# SIK-DIP-board.net
KiCad netlist of a schematic drawn in Altium Designer
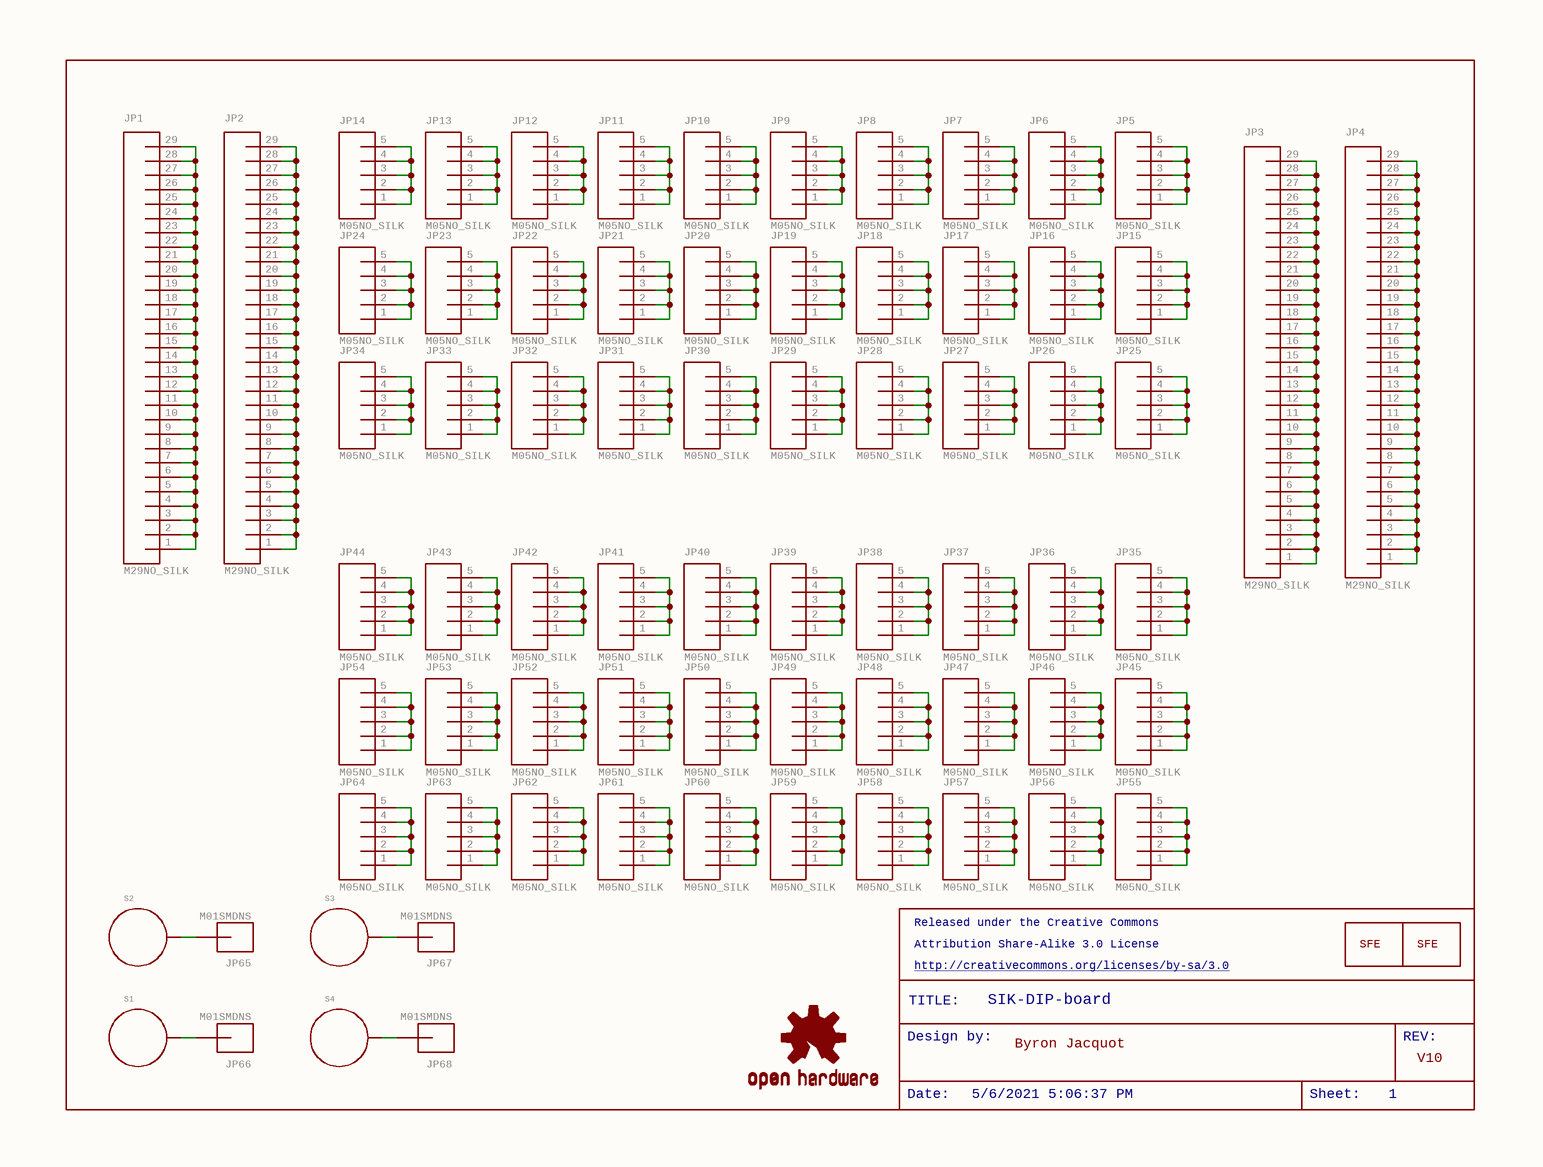
[diagram p0: SIK-DIP-board.SchDoc]

(export (version "E")
  (design (tool "Eeschema 10.0.6"))
  (components
    (comp (ref "JP1")
      (value "M29NO_SILK")
      (footprint "1X29_NO_SILK")
      (description "1x29 .1\" header")
      (libsource (lib "SparkFun-Connectors") (part "M29NO_SILK"))
    )
    (comp (ref "JP2")
      (value "M29NO_SILK")
      (footprint "1X29_NO_SILK")
      (description "1x29 .1\" header")
      (libsource (lib "SparkFun-Connectors") (part "M29NO_SILK"))
    )
    (comp (ref "JP3")
      (value "M29NO_SILK")
      (footprint "1X29_NO_SILK")
      (description "1x29 .1\" header")
      (libsource (lib "SparkFun-Connectors") (part "M29NO_SILK"))
    )
    (comp (ref "JP4")
      (value "M29NO_SILK")
      (footprint "1X29_NO_SILK")
      (description "1x29 .1\" header")
      (libsource (lib "SparkFun-Connectors") (part "M29NO_SILK"))
    )
    (comp (ref "JP5")
      (value "M05NO_SILK")
      (footprint "1X05_NO_SILK")
      (libsource (lib "SparkFun-Connectors") (part "M05NO_SILK"))
    )
    (comp (ref "JP6")
      (value "M05NO_SILK")
      (footprint "1X05_NO_SILK")
      (libsource (lib "SparkFun-Connectors") (part "M05NO_SILK"))
    )
    (comp (ref "JP7")
      (value "M05NO_SILK")
      (footprint "1X05_NO_SILK")
      (libsource (lib "SparkFun-Connectors") (part "M05NO_SILK"))
    )
    (comp (ref "JP8")
      (value "M05NO_SILK")
      (footprint "1X05_NO_SILK")
      (libsource (lib "SparkFun-Connectors") (part "M05NO_SILK"))
    )
    (comp (ref "JP9")
      (value "M05NO_SILK")
      (footprint "1X05_NO_SILK")
      (libsource (lib "SparkFun-Connectors") (part "M05NO_SILK"))
    )
    (comp (ref "JP10")
      (value "M05NO_SILK")
      (footprint "1X05_NO_SILK")
      (libsource (lib "SparkFun-Connectors") (part "M05NO_SILK"))
    )
    (comp (ref "JP11")
      (value "M05NO_SILK")
      (footprint "1X05_NO_SILK")
      (libsource (lib "SparkFun-Connectors") (part "M05NO_SILK"))
    )
    (comp (ref "JP12")
      (value "M05NO_SILK")
      (footprint "1X05_NO_SILK")
      (libsource (lib "SparkFun-Connectors") (part "M05NO_SILK"))
    )
    (comp (ref "JP13")
      (value "M05NO_SILK")
      (footprint "1X05_NO_SILK")
      (libsource (lib "SparkFun-Connectors") (part "M05NO_SILK"))
    )
    (comp (ref "JP14")
      (value "M05NO_SILK")
      (footprint "1X05_NO_SILK")
      (libsource (lib "SparkFun-Connectors") (part "M05NO_SILK"))
    )
    (comp (ref "JP15")
      (value "M05NO_SILK")
      (footprint "1X05_NO_SILK")
      (libsource (lib "SparkFun-Connectors") (part "M05NO_SILK"))
    )
    (comp (ref "JP16")
      (value "M05NO_SILK")
      (footprint "1X05_NO_SILK")
      (libsource (lib "SparkFun-Connectors") (part "M05NO_SILK"))
    )
    (comp (ref "JP17")
      (value "M05NO_SILK")
      (footprint "1X05_NO_SILK")
      (libsource (lib "SparkFun-Connectors") (part "M05NO_SILK"))
    )
    (comp (ref "JP18")
      (value "M05NO_SILK")
      (footprint "1X05_NO_SILK")
      (libsource (lib "SparkFun-Connectors") (part "M05NO_SILK"))
    )
    (comp (ref "JP19")
      (value "M05NO_SILK")
      (footprint "1X05_NO_SILK")
      (libsource (lib "SparkFun-Connectors") (part "M05NO_SILK"))
    )
    (comp (ref "JP20")
      (value "M05NO_SILK")
      (footprint "1X05_NO_SILK")
      (libsource (lib "SparkFun-Connectors") (part "M05NO_SILK"))
    )
    (comp (ref "JP21")
      (value "M05NO_SILK")
      (footprint "1X05_NO_SILK")
      (libsource (lib "SparkFun-Connectors") (part "M05NO_SILK"))
    )
    (comp (ref "JP22")
      (value "M05NO_SILK")
      (footprint "1X05_NO_SILK")
      (libsource (lib "SparkFun-Connectors") (part "M05NO_SILK"))
    )
    (comp (ref "JP23")
      (value "M05NO_SILK")
      (footprint "1X05_NO_SILK")
      (libsource (lib "SparkFun-Connectors") (part "M05NO_SILK"))
    )
    (comp (ref "JP24")
      (value "M05NO_SILK")
      (footprint "1X05_NO_SILK")
      (libsource (lib "SparkFun-Connectors") (part "M05NO_SILK"))
    )
    (comp (ref "JP25")
      (value "M05NO_SILK")
      (footprint "1X05_NO_SILK")
      (libsource (lib "SparkFun-Connectors") (part "M05NO_SILK"))
    )
    (comp (ref "JP26")
      (value "M05NO_SILK")
      (footprint "1X05_NO_SILK")
      (libsource (lib "SparkFun-Connectors") (part "M05NO_SILK"))
    )
    (comp (ref "JP27")
      (value "M05NO_SILK")
      (footprint "1X05_NO_SILK")
      (libsource (lib "SparkFun-Connectors") (part "M05NO_SILK"))
    )
    (comp (ref "JP28")
      (value "M05NO_SILK")
      (footprint "1X05_NO_SILK")
      (libsource (lib "SparkFun-Connectors") (part "M05NO_SILK"))
    )
    (comp (ref "JP29")
      (value "M05NO_SILK")
      (footprint "1X05_NO_SILK")
      (libsource (lib "SparkFun-Connectors") (part "M05NO_SILK"))
    )
    (comp (ref "JP30")
      (value "M05NO_SILK")
      (footprint "1X05_NO_SILK")
      (libsource (lib "SparkFun-Connectors") (part "M05NO_SILK"))
    )
    (comp (ref "JP31")
      (value "M05NO_SILK")
      (footprint "1X05_NO_SILK")
      (libsource (lib "SparkFun-Connectors") (part "M05NO_SILK"))
    )
    (comp (ref "JP32")
      (value "M05NO_SILK")
      (footprint "1X05_NO_SILK")
      (libsource (lib "SparkFun-Connectors") (part "M05NO_SILK"))
    )
    (comp (ref "JP33")
      (value "M05NO_SILK")
      (footprint "1X05_NO_SILK")
      (libsource (lib "SparkFun-Connectors") (part "M05NO_SILK"))
    )
    (comp (ref "JP34")
      (value "M05NO_SILK")
      (footprint "1X05_NO_SILK")
      (libsource (lib "SparkFun-Connectors") (part "M05NO_SILK"))
    )
    (comp (ref "JP35")
      (value "M05NO_SILK")
      (footprint "1X05_NO_SILK")
      (libsource (lib "SparkFun-Connectors") (part "M05NO_SILK"))
    )
    (comp (ref "JP36")
      (value "M05NO_SILK")
      (footprint "1X05_NO_SILK")
      (libsource (lib "SparkFun-Connectors") (part "M05NO_SILK"))
    )
    (comp (ref "JP37")
      (value "M05NO_SILK")
      (footprint "1X05_NO_SILK")
      (libsource (lib "SparkFun-Connectors") (part "M05NO_SILK"))
    )
    (comp (ref "JP38")
      (value "M05NO_SILK")
      (footprint "1X05_NO_SILK")
      (libsource (lib "SparkFun-Connectors") (part "M05NO_SILK"))
    )
    (comp (ref "JP39")
      (value "M05NO_SILK")
      (footprint "1X05_NO_SILK")
      (libsource (lib "SparkFun-Connectors") (part "M05NO_SILK"))
    )
    (comp (ref "JP40")
      (value "M05NO_SILK")
      (footprint "1X05_NO_SILK")
      (libsource (lib "SparkFun-Connectors") (part "M05NO_SILK"))
    )
    (comp (ref "JP41")
      (value "M05NO_SILK")
      (footprint "1X05_NO_SILK")
      (libsource (lib "SparkFun-Connectors") (part "M05NO_SILK"))
    )
    (comp (ref "JP42")
      (value "M05NO_SILK")
      (footprint "1X05_NO_SILK")
      (libsource (lib "SparkFun-Connectors") (part "M05NO_SILK"))
    )
    (comp (ref "JP43")
      (value "M05NO_SILK")
      (footprint "1X05_NO_SILK")
      (libsource (lib "SparkFun-Connectors") (part "M05NO_SILK"))
    )
    (comp (ref "JP44")
      (value "M05NO_SILK")
      (footprint "1X05_NO_SILK")
      (libsource (lib "SparkFun-Connectors") (part "M05NO_SILK"))
    )
    (comp (ref "JP45")
      (value "M05NO_SILK")
      (footprint "1X05_NO_SILK")
      (libsource (lib "SparkFun-Connectors") (part "M05NO_SILK"))
    )
    (comp (ref "JP46")
      (value "M05NO_SILK")
      (footprint "1X05_NO_SILK")
      (libsource (lib "SparkFun-Connectors") (part "M05NO_SILK"))
    )
    (comp (ref "JP47")
      (value "M05NO_SILK")
      (footprint "1X05_NO_SILK")
      (libsource (lib "SparkFun-Connectors") (part "M05NO_SILK"))
    )
    (comp (ref "JP48")
      (value "M05NO_SILK")
      (footprint "1X05_NO_SILK")
      (libsource (lib "SparkFun-Connectors") (part "M05NO_SILK"))
    )
    (comp (ref "JP49")
      (value "M05NO_SILK")
      (footprint "1X05_NO_SILK")
      (libsource (lib "SparkFun-Connectors") (part "M05NO_SILK"))
    )
    (comp (ref "JP50")
      (value "M05NO_SILK")
      (footprint "1X05_NO_SILK")
      (libsource (lib "SparkFun-Connectors") (part "M05NO_SILK"))
    )
    (comp (ref "JP51")
      (value "M05NO_SILK")
      (footprint "1X05_NO_SILK")
      (libsource (lib "SparkFun-Connectors") (part "M05NO_SILK"))
    )
    (comp (ref "JP52")
      (value "M05NO_SILK")
      (footprint "1X05_NO_SILK")
      (libsource (lib "SparkFun-Connectors") (part "M05NO_SILK"))
    )
    (comp (ref "JP53")
      (value "M05NO_SILK")
      (footprint "1X05_NO_SILK")
      (libsource (lib "SparkFun-Connectors") (part "M05NO_SILK"))
    )
    (comp (ref "JP54")
      (value "M05NO_SILK")
      (footprint "1X05_NO_SILK")
      (libsource (lib "SparkFun-Connectors") (part "M05NO_SILK"))
    )
    (comp (ref "JP55")
      (value "M05NO_SILK")
      (footprint "1X05_NO_SILK")
      (libsource (lib "SparkFun-Connectors") (part "M05NO_SILK"))
    )
    (comp (ref "JP56")
      (value "M05NO_SILK")
      (footprint "1X05_NO_SILK")
      (libsource (lib "SparkFun-Connectors") (part "M05NO_SILK"))
    )
    (comp (ref "JP57")
      (value "M05NO_SILK")
      (footprint "1X05_NO_SILK")
      (libsource (lib "SparkFun-Connectors") (part "M05NO_SILK"))
    )
    (comp (ref "JP58")
      (value "M05NO_SILK")
      (footprint "1X05_NO_SILK")
      (libsource (lib "SparkFun-Connectors") (part "M05NO_SILK"))
    )
    (comp (ref "JP59")
      (value "M05NO_SILK")
      (footprint "1X05_NO_SILK")
      (libsource (lib "SparkFun-Connectors") (part "M05NO_SILK"))
    )
    (comp (ref "JP60")
      (value "M05NO_SILK")
      (footprint "1X05_NO_SILK")
      (libsource (lib "SparkFun-Connectors") (part "M05NO_SILK"))
    )
    (comp (ref "JP61")
      (value "M05NO_SILK")
      (footprint "1X05_NO_SILK")
      (libsource (lib "SparkFun-Connectors") (part "M05NO_SILK"))
    )
    (comp (ref "JP62")
      (value "M05NO_SILK")
      (footprint "1X05_NO_SILK")
      (libsource (lib "SparkFun-Connectors") (part "M05NO_SILK"))
    )
    (comp (ref "JP63")
      (value "M05NO_SILK")
      (footprint "1X05_NO_SILK")
      (libsource (lib "SparkFun-Connectors") (part "M05NO_SILK"))
    )
    (comp (ref "JP64")
      (value "M05NO_SILK")
      (footprint "1X05_NO_SILK")
      (libsource (lib "SparkFun-Connectors") (part "M05NO_SILK"))
    )
    (comp (ref "JP65")
      (value "M01SMDNS")
      (footprint "1X01NS")
      (libsource (lib "SparkFun-Connectors") (part "M01SMDNS"))
    )
    (comp (ref "JP66")
      (value "M01SMDNS")
      (footprint "1X01NS")
      (libsource (lib "SparkFun-Connectors") (part "M01SMDNS"))
    )
    (comp (ref "JP67")
      (value "M01SMDNS")
      (footprint "1X01NS")
      (libsource (lib "SparkFun-Connectors") (part "M01SMDNS"))
    )
    (comp (ref "JP68")
      (value "M01SMDNS")
      (footprint "1X01NS")
      (libsource (lib "SparkFun-Connectors") (part "M01SMDNS"))
    )
    (comp (ref "LOGO1")
      (value "LOGO-SFECP")
      (footprint "SFE-LOGO-FLAME-COPPER")
      (description "Spark Fun Electronics PCB LogoThis is the standard Spark Fun Electronics PCB logo.")
      (fields (field (name "SFE") "SFE"))
      (libsource (lib "SparkFun-Aesthetics") (part "LOGO-SFECP"))
    )
    (comp (ref "LOGO2")
      (value "LOGO-SFENEW")
      (footprint "SFE-NEW-WEBLOGO")
      (description "Spark Fun Electronics PCB LogoThis is the standard Spark Fun Electronics PCB logo.")
      (fields (field (name "SFE") "SFE"))
      (libsource (lib "SparkFun-Aesthetics") (part "LOGO-SFENEW"))
    )
    (comp (ref "LOGO3")
      (value "OSHW-LOGOS")
      (footprint "OSHW-LOGO-S")
      (libsource (lib "SparkFun-Aesthetics") (part "OSHW-LOGOS"))
    )
    (comp (ref "S1")
      (value "STANDOFF_ELECTRICAL")
      (footprint "STANDOFF-ELECTRICAL")
      (libsource (lib "SparkFun-Electromechanical") (part "STANDOFF_ELECTRICAL"))
    )
    (comp (ref "S2")
      (value "STANDOFF_ELECTRICAL")
      (footprint "STANDOFF-ELECTRICAL")
      (libsource (lib "SparkFun-Electromechanical") (part "STANDOFF_ELECTRICAL"))
    )
    (comp (ref "S3")
      (value "STANDOFF_ELECTRICAL")
      (footprint "STANDOFF-ELECTRICAL")
      (libsource (lib "SparkFun-Electromechanical") (part "STANDOFF_ELECTRICAL"))
    )
    (comp (ref "S4")
      (value "STANDOFF_ELECTRICAL")
      (footprint "STANDOFF-ELECTRICAL")
      (libsource (lib "SparkFun-Electromechanical") (part "STANDOFF_ELECTRICAL"))
    )
  )
  (nets
    (net (code "1") (name "Net-(JP1-Pad1)") (class "Default")
      (node (ref "JP1") (pin "1") (pinfunction "1_1") (pintype "passive"))
      (node (ref "JP1") (pin "10") (pinfunction "10_10") (pintype "passive"))
      (node (ref "JP1") (pin "11") (pinfunction "11_11") (pintype "passive"))
      (node (ref "JP1") (pin "12") (pinfunction "12_12") (pintype "passive"))
      (node (ref "JP1") (pin "13") (pinfunction "13_13") (pintype "passive"))
      (node (ref "JP1") (pin "14") (pinfunction "14_14") (pintype "passive"))
      (node (ref "JP1") (pin "15") (pinfunction "15_15") (pintype "passive"))
      (node (ref "JP1") (pin "16") (pinfunction "16_16") (pintype "passive"))
      (node (ref "JP1") (pin "17") (pinfunction "17_17") (pintype "passive"))
      (node (ref "JP1") (pin "18") (pinfunction "18_18") (pintype "passive"))
      (node (ref "JP1") (pin "19") (pinfunction "19_19") (pintype "passive"))
      (node (ref "JP1") (pin "2") (pinfunction "2_2") (pintype "passive"))
      (node (ref "JP1") (pin "20") (pinfunction "20_20") (pintype "passive"))
      (node (ref "JP1") (pin "21") (pinfunction "21_21") (pintype "passive"))
      (node (ref "JP1") (pin "22") (pinfunction "22_22") (pintype "passive"))
      (node (ref "JP1") (pin "23") (pinfunction "23_23") (pintype "passive"))
      (node (ref "JP1") (pin "24") (pinfunction "24_24") (pintype "passive"))
      (node (ref "JP1") (pin "25") (pinfunction "25_25") (pintype "passive"))
      (node (ref "JP1") (pin "26") (pinfunction "26_26") (pintype "passive"))
      (node (ref "JP1") (pin "27") (pinfunction "27_27") (pintype "passive"))
      (node (ref "JP1") (pin "28") (pinfunction "28_28") (pintype "passive"))
      (node (ref "JP1") (pin "29") (pinfunction "29_29") (pintype "passive"))
      (node (ref "JP1") (pin "3") (pinfunction "3_3") (pintype "passive"))
      (node (ref "JP1") (pin "4") (pinfunction "4_4") (pintype "passive"))
      (node (ref "JP1") (pin "5") (pinfunction "5_5") (pintype "passive"))
      (node (ref "JP1") (pin "6") (pinfunction "6_6") (pintype "passive"))
      (node (ref "JP1") (pin "7") (pinfunction "7_7") (pintype "passive"))
      (node (ref "JP1") (pin "8") (pinfunction "8_8") (pintype "passive"))
      (node (ref "JP1") (pin "9") (pinfunction "9_9") (pintype "passive"))
    )
    (net (code "2") (name "Net-(JP2-Pad1)") (class "Default")
      (node (ref "JP2") (pin "1") (pinfunction "1_1") (pintype "passive"))
      (node (ref "JP2") (pin "10") (pinfunction "10_10") (pintype "passive"))
      (node (ref "JP2") (pin "11") (pinfunction "11_11") (pintype "passive"))
      (node (ref "JP2") (pin "12") (pinfunction "12_12") (pintype "passive"))
      (node (ref "JP2") (pin "13") (pinfunction "13_13") (pintype "passive"))
      (node (ref "JP2") (pin "14") (pinfunction "14_14") (pintype "passive"))
      (node (ref "JP2") (pin "15") (pinfunction "15_15") (pintype "passive"))
      (node (ref "JP2") (pin "16") (pinfunction "16_16") (pintype "passive"))
      (node (ref "JP2") (pin "17") (pinfunction "17_17") (pintype "passive"))
      (node (ref "JP2") (pin "18") (pinfunction "18_18") (pintype "passive"))
      (node (ref "JP2") (pin "19") (pinfunction "19_19") (pintype "passive"))
      (node (ref "JP2") (pin "2") (pinfunction "2_2") (pintype "passive"))
      (node (ref "JP2") (pin "20") (pinfunction "20_20") (pintype "passive"))
      (node (ref "JP2") (pin "21") (pinfunction "21_21") (pintype "passive"))
      (node (ref "JP2") (pin "22") (pinfunction "22_22") (pintype "passive"))
      (node (ref "JP2") (pin "23") (pinfunction "23_23") (pintype "passive"))
      (node (ref "JP2") (pin "24") (pinfunction "24_24") (pintype "passive"))
      (node (ref "JP2") (pin "25") (pinfunction "25_25") (pintype "passive"))
      (node (ref "JP2") (pin "26") (pinfunction "26_26") (pintype "passive"))
      (node (ref "JP2") (pin "27") (pinfunction "27_27") (pintype "passive"))
      (node (ref "JP2") (pin "28") (pinfunction "28_28") (pintype "passive"))
      (node (ref "JP2") (pin "29") (pinfunction "29_29") (pintype "passive"))
      (node (ref "JP2") (pin "3") (pinfunction "3_3") (pintype "passive"))
      (node (ref "JP2") (pin "4") (pinfunction "4_4") (pintype "passive"))
      (node (ref "JP2") (pin "5") (pinfunction "5_5") (pintype "passive"))
      (node (ref "JP2") (pin "6") (pinfunction "6_6") (pintype "passive"))
      (node (ref "JP2") (pin "7") (pinfunction "7_7") (pintype "passive"))
      (node (ref "JP2") (pin "8") (pinfunction "8_8") (pintype "passive"))
      (node (ref "JP2") (pin "9") (pinfunction "9_9") (pintype "passive"))
    )
    (net (code "3") (name "Net-(JP3-Pad1)") (class "Default")
      (node (ref "JP3") (pin "1") (pinfunction "1_1") (pintype "passive"))
      (node (ref "JP3") (pin "10") (pinfunction "10_10") (pintype "passive"))
      (node (ref "JP3") (pin "11") (pinfunction "11_11") (pintype "passive"))
      (node (ref "JP3") (pin "12") (pinfunction "12_12") (pintype "passive"))
      (node (ref "JP3") (pin "13") (pinfunction "13_13") (pintype "passive"))
      (node (ref "JP3") (pin "14") (pinfunction "14_14") (pintype "passive"))
      (node (ref "JP3") (pin "15") (pinfunction "15_15") (pintype "passive"))
      (node (ref "JP3") (pin "16") (pinfunction "16_16") (pintype "passive"))
      (node (ref "JP3") (pin "17") (pinfunction "17_17") (pintype "passive"))
      (node (ref "JP3") (pin "18") (pinfunction "18_18") (pintype "passive"))
      (node (ref "JP3") (pin "19") (pinfunction "19_19") (pintype "passive"))
      (node (ref "JP3") (pin "2") (pinfunction "2_2") (pintype "passive"))
      (node (ref "JP3") (pin "20") (pinfunction "20_20") (pintype "passive"))
      (node (ref "JP3") (pin "21") (pinfunction "21_21") (pintype "passive"))
      (node (ref "JP3") (pin "22") (pinfunction "22_22") (pintype "passive"))
      (node (ref "JP3") (pin "23") (pinfunction "23_23") (pintype "passive"))
      (node (ref "JP3") (pin "24") (pinfunction "24_24") (pintype "passive"))
      (node (ref "JP3") (pin "25") (pinfunction "25_25") (pintype "passive"))
      (node (ref "JP3") (pin "26") (pinfunction "26_26") (pintype "passive"))
      (node (ref "JP3") (pin "27") (pinfunction "27_27") (pintype "passive"))
      (node (ref "JP3") (pin "28") (pinfunction "28_28") (pintype "passive"))
      (node (ref "JP3") (pin "29") (pinfunction "29_29") (pintype "passive"))
      (node (ref "JP3") (pin "3") (pinfunction "3_3") (pintype "passive"))
      (node (ref "JP3") (pin "4") (pinfunction "4_4") (pintype "passive"))
      (node (ref "JP3") (pin "5") (pinfunction "5_5") (pintype "passive"))
      (node (ref "JP3") (pin "6") (pinfunction "6_6") (pintype "passive"))
      (node (ref "JP3") (pin "7") (pinfunction "7_7") (pintype "passive"))
      (node (ref "JP3") (pin "8") (pinfunction "8_8") (pintype "passive"))
      (node (ref "JP3") (pin "9") (pinfunction "9_9") (pintype "passive"))
    )
    (net (code "4") (name "Net-(JP4-Pad1)") (class "Default")
      (node (ref "JP4") (pin "1") (pinfunction "1_1") (pintype "passive"))
      (node (ref "JP4") (pin "10") (pinfunction "10_10") (pintype "passive"))
      (node (ref "JP4") (pin "11") (pinfunction "11_11") (pintype "passive"))
      (node (ref "JP4") (pin "12") (pinfunction "12_12") (pintype "passive"))
      (node (ref "JP4") (pin "13") (pinfunction "13_13") (pintype "passive"))
      (node (ref "JP4") (pin "14") (pinfunction "14_14") (pintype "passive"))
      (node (ref "JP4") (pin "15") (pinfunction "15_15") (pintype "passive"))
      (node (ref "JP4") (pin "16") (pinfunction "16_16") (pintype "passive"))
      (node (ref "JP4") (pin "17") (pinfunction "17_17") (pintype "passive"))
      (node (ref "JP4") (pin "18") (pinfunction "18_18") (pintype "passive"))
      (node (ref "JP4") (pin "19") (pinfunction "19_19") (pintype "passive"))
      (node (ref "JP4") (pin "2") (pinfunction "2_2") (pintype "passive"))
      (node (ref "JP4") (pin "20") (pinfunction "20_20") (pintype "passive"))
      (node (ref "JP4") (pin "21") (pinfunction "21_21") (pintype "passive"))
      (node (ref "JP4") (pin "22") (pinfunction "22_22") (pintype "passive"))
      (node (ref "JP4") (pin "23") (pinfunction "23_23") (pintype "passive"))
      (node (ref "JP4") (pin "24") (pinfunction "24_24") (pintype "passive"))
      (node (ref "JP4") (pin "25") (pinfunction "25_25") (pintype "passive"))
      (node (ref "JP4") (pin "26") (pinfunction "26_26") (pintype "passive"))
      (node (ref "JP4") (pin "27") (pinfunction "27_27") (pintype "passive"))
      (node (ref "JP4") (pin "28") (pinfunction "28_28") (pintype "passive"))
      (node (ref "JP4") (pin "29") (pinfunction "29_29") (pintype "passive"))
      (node (ref "JP4") (pin "3") (pinfunction "3_3") (pintype "passive"))
      (node (ref "JP4") (pin "4") (pinfunction "4_4") (pintype "passive"))
      (node (ref "JP4") (pin "5") (pinfunction "5_5") (pintype "passive"))
      (node (ref "JP4") (pin "6") (pinfunction "6_6") (pintype "passive"))
      (node (ref "JP4") (pin "7") (pinfunction "7_7") (pintype "passive"))
      (node (ref "JP4") (pin "8") (pinfunction "8_8") (pintype "passive"))
      (node (ref "JP4") (pin "9") (pinfunction "9_9") (pintype "passive"))
    )
    (net (code "5") (name "Net-(JP5-Pad1)") (class "Default")
      (node (ref "JP5") (pin "1") (pinfunction "1_1") (pintype "passive"))
      (node (ref "JP5") (pin "2") (pinfunction "2_2") (pintype "passive"))
      (node (ref "JP5") (pin "3") (pinfunction "3_3") (pintype "passive"))
      (node (ref "JP5") (pin "4") (pinfunction "4_4") (pintype "passive"))
      (node (ref "JP5") (pin "5") (pinfunction "5_5") (pintype "passive"))
    )
    (net (code "6") (name "Net-(JP6-Pad1)") (class "Default")
      (node (ref "JP6") (pin "1") (pinfunction "1_1") (pintype "passive"))
      (node (ref "JP6") (pin "2") (pinfunction "2_2") (pintype "passive"))
      (node (ref "JP6") (pin "3") (pinfunction "3_3") (pintype "passive"))
      (node (ref "JP6") (pin "4") (pinfunction "4_4") (pintype "passive"))
      (node (ref "JP6") (pin "5") (pinfunction "5_5") (pintype "passive"))
    )
    (net (code "7") (name "Net-(JP7-Pad1)") (class "Default")
      (node (ref "JP7") (pin "1") (pinfunction "1_1") (pintype "passive"))
      (node (ref "JP7") (pin "2") (pinfunction "2_2") (pintype "passive"))
      (node (ref "JP7") (pin "3") (pinfunction "3_3") (pintype "passive"))
      (node (ref "JP7") (pin "4") (pinfunction "4_4") (pintype "passive"))
      (node (ref "JP7") (pin "5") (pinfunction "5_5") (pintype "passive"))
    )
    (net (code "8") (name "Net-(JP8-Pad1)") (class "Default")
      (node (ref "JP8") (pin "1") (pinfunction "1_1") (pintype "passive"))
      (node (ref "JP8") (pin "2") (pinfunction "2_2") (pintype "passive"))
      (node (ref "JP8") (pin "3") (pinfunction "3_3") (pintype "passive"))
      (node (ref "JP8") (pin "4") (pinfunction "4_4") (pintype "passive"))
      (node (ref "JP8") (pin "5") (pinfunction "5_5") (pintype "passive"))
    )
    (net (code "9") (name "Net-(JP9-Pad1)") (class "Default")
      (node (ref "JP9") (pin "1") (pinfunction "1_1") (pintype "passive"))
      (node (ref "JP9") (pin "2") (pinfunction "2_2") (pintype "passive"))
      (node (ref "JP9") (pin "3") (pinfunction "3_3") (pintype "passive"))
      (node (ref "JP9") (pin "4") (pinfunction "4_4") (pintype "passive"))
      (node (ref "JP9") (pin "5") (pinfunction "5_5") (pintype "passive"))
    )
    (net (code "10") (name "Net-(JP10-Pad1)") (class "Default")
      (node (ref "JP10") (pin "1") (pinfunction "1_1") (pintype "passive"))
      (node (ref "JP10") (pin "2") (pinfunction "2_2") (pintype "passive"))
      (node (ref "JP10") (pin "3") (pinfunction "3_3") (pintype "passive"))
      (node (ref "JP10") (pin "4") (pinfunction "4_4") (pintype "passive"))
      (node (ref "JP10") (pin "5") (pinfunction "5_5") (pintype "passive"))
    )
    (net (code "11") (name "Net-(JP11-Pad1)") (class "Default")
      (node (ref "JP11") (pin "1") (pinfunction "1_1") (pintype "passive"))
      (node (ref "JP11") (pin "2") (pinfunction "2_2") (pintype "passive"))
      (node (ref "JP11") (pin "3") (pinfunction "3_3") (pintype "passive"))
      (node (ref "JP11") (pin "4") (pinfunction "4_4") (pintype "passive"))
      (node (ref "JP11") (pin "5") (pinfunction "5_5") (pintype "passive"))
    )
    (net (code "12") (name "Net-(JP12-Pad1)") (class "Default")
      (node (ref "JP12") (pin "1") (pinfunction "1_1") (pintype "passive"))
      (node (ref "JP12") (pin "2") (pinfunction "2_2") (pintype "passive"))
      (node (ref "JP12") (pin "3") (pinfunction "3_3") (pintype "passive"))
      (node (ref "JP12") (pin "4") (pinfunction "4_4") (pintype "passive"))
      (node (ref "JP12") (pin "5") (pinfunction "5_5") (pintype "passive"))
    )
    (net (code "13") (name "Net-(JP13-Pad1)") (class "Default")
      (node (ref "JP13") (pin "1") (pinfunction "1_1") (pintype "passive"))
      (node (ref "JP13") (pin "2") (pinfunction "2_2") (pintype "passive"))
      (node (ref "JP13") (pin "3") (pinfunction "3_3") (pintype "passive"))
      (node (ref "JP13") (pin "4") (pinfunction "4_4") (pintype "passive"))
      (node (ref "JP13") (pin "5") (pinfunction "5_5") (pintype "passive"))
    )
    (net (code "14") (name "Net-(JP14-Pad1)") (class "Default")
      (node (ref "JP14") (pin "1") (pinfunction "1_1") (pintype "passive"))
      (node (ref "JP14") (pin "2") (pinfunction "2_2") (pintype "passive"))
      (node (ref "JP14") (pin "3") (pinfunction "3_3") (pintype "passive"))
      (node (ref "JP14") (pin "4") (pinfunction "4_4") (pintype "passive"))
      (node (ref "JP14") (pin "5") (pinfunction "5_5") (pintype "passive"))
    )
    (net (code "15") (name "Net-(JP15-Pad1)") (class "Default")
      (node (ref "JP15") (pin "1") (pinfunction "1_1") (pintype "passive"))
      (node (ref "JP15") (pin "2") (pinfunction "2_2") (pintype "passive"))
      (node (ref "JP15") (pin "3") (pinfunction "3_3") (pintype "passive"))
      (node (ref "JP15") (pin "4") (pinfunction "4_4") (pintype "passive"))
      (node (ref "JP15") (pin "5") (pinfunction "5_5") (pintype "passive"))
    )
    (net (code "16") (name "Net-(JP16-Pad1)") (class "Default")
      (node (ref "JP16") (pin "1") (pinfunction "1_1") (pintype "passive"))
      (node (ref "JP16") (pin "2") (pinfunction "2_2") (pintype "passive"))
      (node (ref "JP16") (pin "3") (pinfunction "3_3") (pintype "passive"))
      (node (ref "JP16") (pin "4") (pinfunction "4_4") (pintype "passive"))
      (node (ref "JP16") (pin "5") (pinfunction "5_5") (pintype "passive"))
    )
    (net (code "17") (name "Net-(JP17-Pad1)") (class "Default")
      (node (ref "JP17") (pin "1") (pinfunction "1_1") (pintype "passive"))
      (node (ref "JP17") (pin "2") (pinfunction "2_2") (pintype "passive"))
      (node (ref "JP17") (pin "3") (pinfunction "3_3") (pintype "passive"))
      (node (ref "JP17") (pin "4") (pinfunction "4_4") (pintype "passive"))
      (node (ref "JP17") (pin "5") (pinfunction "5_5") (pintype "passive"))
    )
    (net (code "18") (name "Net-(JP18-Pad1)") (class "Default")
      (node (ref "JP18") (pin "1") (pinfunction "1_1") (pintype "passive"))
      (node (ref "JP18") (pin "2") (pinfunction "2_2") (pintype "passive"))
      (node (ref "JP18") (pin "3") (pinfunction "3_3") (pintype "passive"))
      (node (ref "JP18") (pin "4") (pinfunction "4_4") (pintype "passive"))
      (node (ref "JP18") (pin "5") (pinfunction "5_5") (pintype "passive"))
    )
    (net (code "19") (name "Net-(JP19-Pad1)") (class "Default")
      (node (ref "JP19") (pin "1") (pinfunction "1_1") (pintype "passive"))
      (node (ref "JP19") (pin "2") (pinfunction "2_2") (pintype "passive"))
      (node (ref "JP19") (pin "3") (pinfunction "3_3") (pintype "passive"))
      (node (ref "JP19") (pin "4") (pinfunction "4_4") (pintype "passive"))
      (node (ref "JP19") (pin "5") (pinfunction "5_5") (pintype "passive"))
    )
    (net (code "20") (name "Net-(JP20-Pad1)") (class "Default")
      (node (ref "JP20") (pin "1") (pinfunction "1_1") (pintype "passive"))
      (node (ref "JP20") (pin "2") (pinfunction "2_2") (pintype "passive"))
      (node (ref "JP20") (pin "3") (pinfunction "3_3") (pintype "passive"))
      (node (ref "JP20") (pin "4") (pinfunction "4_4") (pintype "passive"))
      (node (ref "JP20") (pin "5") (pinfunction "5_5") (pintype "passive"))
    )
    (net (code "21") (name "Net-(JP21-Pad1)") (class "Default")
      (node (ref "JP21") (pin "1") (pinfunction "1_1") (pintype "passive"))
      (node (ref "JP21") (pin "2") (pinfunction "2_2") (pintype "passive"))
      (node (ref "JP21") (pin "3") (pinfunction "3_3") (pintype "passive"))
      (node (ref "JP21") (pin "4") (pinfunction "4_4") (pintype "passive"))
      (node (ref "JP21") (pin "5") (pinfunction "5_5") (pintype "passive"))
    )
    (net (code "22") (name "Net-(JP22-Pad1)") (class "Default")
      (node (ref "JP22") (pin "1") (pinfunction "1_1") (pintype "passive"))
      (node (ref "JP22") (pin "2") (pinfunction "2_2") (pintype "passive"))
      (node (ref "JP22") (pin "3") (pinfunction "3_3") (pintype "passive"))
      (node (ref "JP22") (pin "4") (pinfunction "4_4") (pintype "passive"))
      (node (ref "JP22") (pin "5") (pinfunction "5_5") (pintype "passive"))
    )
    (net (code "23") (name "Net-(JP23-Pad1)") (class "Default")
      (node (ref "JP23") (pin "1") (pinfunction "1_1") (pintype "passive"))
      (node (ref "JP23") (pin "2") (pinfunction "2_2") (pintype "passive"))
      (node (ref "JP23") (pin "3") (pinfunction "3_3") (pintype "passive"))
      (node (ref "JP23") (pin "4") (pinfunction "4_4") (pintype "passive"))
      (node (ref "JP23") (pin "5") (pinfunction "5_5") (pintype "passive"))
    )
    (net (code "24") (name "Net-(JP24-Pad1)") (class "Default")
      (node (ref "JP24") (pin "1") (pinfunction "1_1") (pintype "passive"))
      (node (ref "JP24") (pin "2") (pinfunction "2_2") (pintype "passive"))
      (node (ref "JP24") (pin "3") (pinfunction "3_3") (pintype "passive"))
      (node (ref "JP24") (pin "4") (pinfunction "4_4") (pintype "passive"))
      (node (ref "JP24") (pin "5") (pinfunction "5_5") (pintype "passive"))
    )
    (net (code "25") (name "Net-(JP25-Pad1)") (class "Default")
      (node (ref "JP25") (pin "1") (pinfunction "1_1") (pintype "passive"))
      (node (ref "JP25") (pin "2") (pinfunction "2_2") (pintype "passive"))
      (node (ref "JP25") (pin "3") (pinfunction "3_3") (pintype "passive"))
      (node (ref "JP25") (pin "4") (pinfunction "4_4") (pintype "passive"))
      (node (ref "JP25") (pin "5") (pinfunction "5_5") (pintype "passive"))
    )
    (net (code "26") (name "Net-(JP26-Pad1)") (class "Default")
      (node (ref "JP26") (pin "1") (pinfunction "1_1") (pintype "passive"))
      (node (ref "JP26") (pin "2") (pinfunction "2_2") (pintype "passive"))
      (node (ref "JP26") (pin "3") (pinfunction "3_3") (pintype "passive"))
      (node (ref "JP26") (pin "4") (pinfunction "4_4") (pintype "passive"))
      (node (ref "JP26") (pin "5") (pinfunction "5_5") (pintype "passive"))
    )
    (net (code "27") (name "Net-(JP27-Pad1)") (class "Default")
      (node (ref "JP27") (pin "1") (pinfunction "1_1") (pintype "passive"))
      (node (ref "JP27") (pin "2") (pinfunction "2_2") (pintype "passive"))
      (node (ref "JP27") (pin "3") (pinfunction "3_3") (pintype "passive"))
      (node (ref "JP27") (pin "4") (pinfunction "4_4") (pintype "passive"))
      (node (ref "JP27") (pin "5") (pinfunction "5_5") (pintype "passive"))
    )
    (net (code "28") (name "Net-(JP28-Pad1)") (class "Default")
      (node (ref "JP28") (pin "1") (pinfunction "1_1") (pintype "passive"))
      (node (ref "JP28") (pin "2") (pinfunction "2_2") (pintype "passive"))
      (node (ref "JP28") (pin "3") (pinfunction "3_3") (pintype "passive"))
      (node (ref "JP28") (pin "4") (pinfunction "4_4") (pintype "passive"))
      (node (ref "JP28") (pin "5") (pinfunction "5_5") (pintype "passive"))
    )
    (net (code "29") (name "Net-(JP29-Pad1)") (class "Default")
      (node (ref "JP29") (pin "1") (pinfunction "1_1") (pintype "passive"))
      (node (ref "JP29") (pin "2") (pinfunction "2_2") (pintype "passive"))
      (node (ref "JP29") (pin "3") (pinfunction "3_3") (pintype "passive"))
      (node (ref "JP29") (pin "4") (pinfunction "4_4") (pintype "passive"))
      (node (ref "JP29") (pin "5") (pinfunction "5_5") (pintype "passive"))
    )
    (net (code "30") (name "Net-(JP30-Pad1)") (class "Default")
      (node (ref "JP30") (pin "1") (pinfunction "1_1") (pintype "passive"))
      (node (ref "JP30") (pin "2") (pinfunction "2_2") (pintype "passive"))
      (node (ref "JP30") (pin "3") (pinfunction "3_3") (pintype "passive"))
      (node (ref "JP30") (pin "4") (pinfunction "4_4") (pintype "passive"))
      (node (ref "JP30") (pin "5") (pinfunction "5_5") (pintype "passive"))
    )
    (net (code "31") (name "Net-(JP31-Pad1)") (class "Default")
      (node (ref "JP31") (pin "1") (pinfunction "1_1") (pintype "passive"))
      (node (ref "JP31") (pin "2") (pinfunction "2_2") (pintype "passive"))
      (node (ref "JP31") (pin "3") (pinfunction "3_3") (pintype "passive"))
      (node (ref "JP31") (pin "4") (pinfunction "4_4") (pintype "passive"))
      (node (ref "JP31") (pin "5") (pinfunction "5_5") (pintype "passive"))
    )
    (net (code "32") (name "Net-(JP32-Pad1)") (class "Default")
      (node (ref "JP32") (pin "1") (pinfunction "1_1") (pintype "passive"))
      (node (ref "JP32") (pin "2") (pinfunction "2_2") (pintype "passive"))
      (node (ref "JP32") (pin "3") (pinfunction "3_3") (pintype "passive"))
      (node (ref "JP32") (pin "4") (pinfunction "4_4") (pintype "passive"))
      (node (ref "JP32") (pin "5") (pinfunction "5_5") (pintype "passive"))
    )
    (net (code "33") (name "Net-(JP33-Pad1)") (class "Default")
      (node (ref "JP33") (pin "1") (pinfunction "1_1") (pintype "passive"))
      (node (ref "JP33") (pin "2") (pinfunction "2_2") (pintype "passive"))
      (node (ref "JP33") (pin "3") (pinfunction "3_3") (pintype "passive"))
      (node (ref "JP33") (pin "4") (pinfunction "4_4") (pintype "passive"))
      (node (ref "JP33") (pin "5") (pinfunction "5_5") (pintype "passive"))
    )
    (net (code "34") (name "Net-(JP34-Pad1)") (class "Default")
      (node (ref "JP34") (pin "1") (pinfunction "1_1") (pintype "passive"))
      (node (ref "JP34") (pin "2") (pinfunction "2_2") (pintype "passive"))
      (node (ref "JP34") (pin "3") (pinfunction "3_3") (pintype "passive"))
      (node (ref "JP34") (pin "4") (pinfunction "4_4") (pintype "passive"))
      (node (ref "JP34") (pin "5") (pinfunction "5_5") (pintype "passive"))
    )
    (net (code "35") (name "Net-(JP35-Pad1)") (class "Default")
      (node (ref "JP35") (pin "1") (pinfunction "1_1") (pintype "passive"))
      (node (ref "JP35") (pin "2") (pinfunction "2_2") (pintype "passive"))
      (node (ref "JP35") (pin "3") (pinfunction "3_3") (pintype "passive"))
      (node (ref "JP35") (pin "4") (pinfunction "4_4") (pintype "passive"))
      (node (ref "JP35") (pin "5") (pinfunction "5_5") (pintype "passive"))
    )
    (net (code "36") (name "Net-(JP36-Pad1)") (class "Default")
      (node (ref "JP36") (pin "1") (pinfunction "1_1") (pintype "passive"))
      (node (ref "JP36") (pin "2") (pinfunction "2_2") (pintype "passive"))
      (node (ref "JP36") (pin "3") (pinfunction "3_3") (pintype "passive"))
      (node (ref "JP36") (pin "4") (pinfunction "4_4") (pintype "passive"))
      (node (ref "JP36") (pin "5") (pinfunction "5_5") (pintype "passive"))
    )
    (net (code "37") (name "Net-(JP37-Pad1)") (class "Default")
      (node (ref "JP37") (pin "1") (pinfunction "1_1") (pintype "passive"))
      (node (ref "JP37") (pin "2") (pinfunction "2_2") (pintype "passive"))
      (node (ref "JP37") (pin "3") (pinfunction "3_3") (pintype "passive"))
      (node (ref "JP37") (pin "4") (pinfunction "4_4") (pintype "passive"))
      (node (ref "JP37") (pin "5") (pinfunction "5_5") (pintype "passive"))
    )
    (net (code "38") (name "Net-(JP38-Pad1)") (class "Default")
      (node (ref "JP38") (pin "1") (pinfunction "1_1") (pintype "passive"))
      (node (ref "JP38") (pin "2") (pinfunction "2_2") (pintype "passive"))
      (node (ref "JP38") (pin "3") (pinfunction "3_3") (pintype "passive"))
      (node (ref "JP38") (pin "4") (pinfunction "4_4") (pintype "passive"))
      (node (ref "JP38") (pin "5") (pinfunction "5_5") (pintype "passive"))
    )
    (net (code "39") (name "Net-(JP39-Pad1)") (class "Default")
      (node (ref "JP39") (pin "1") (pinfunction "1_1") (pintype "passive"))
      (node (ref "JP39") (pin "2") (pinfunction "2_2") (pintype "passive"))
      (node (ref "JP39") (pin "3") (pinfunction "3_3") (pintype "passive"))
      (node (ref "JP39") (pin "4") (pinfunction "4_4") (pintype "passive"))
      (node (ref "JP39") (pin "5") (pinfunction "5_5") (pintype "passive"))
    )
    (net (code "40") (name "Net-(JP40-Pad1)") (class "Default")
      (node (ref "JP40") (pin "1") (pinfunction "1_1") (pintype "passive"))
      (node (ref "JP40") (pin "2") (pinfunction "2_2") (pintype "passive"))
      (node (ref "JP40") (pin "3") (pinfunction "3_3") (pintype "passive"))
      (node (ref "JP40") (pin "4") (pinfunction "4_4") (pintype "passive"))
      (node (ref "JP40") (pin "5") (pinfunction "5_5") (pintype "passive"))
    )
    (net (code "41") (name "Net-(JP41-Pad1)") (class "Default")
      (node (ref "JP41") (pin "1") (pinfunction "1_1") (pintype "passive"))
      (node (ref "JP41") (pin "2") (pinfunction "2_2") (pintype "passive"))
      (node (ref "JP41") (pin "3") (pinfunction "3_3") (pintype "passive"))
      (node (ref "JP41") (pin "4") (pinfunction "4_4") (pintype "passive"))
      (node (ref "JP41") (pin "5") (pinfunction "5_5") (pintype "passive"))
    )
    (net (code "42") (name "Net-(JP42-Pad1)") (class "Default")
      (node (ref "JP42") (pin "1") (pinfunction "1_1") (pintype "passive"))
      (node (ref "JP42") (pin "2") (pinfunction "2_2") (pintype "passive"))
      (node (ref "JP42") (pin "3") (pinfunction "3_3") (pintype "passive"))
      (node (ref "JP42") (pin "4") (pinfunction "4_4") (pintype "passive"))
      (node (ref "JP42") (pin "5") (pinfunction "5_5") (pintype "passive"))
    )
    (net (code "43") (name "Net-(JP43-Pad1)") (class "Default")
      (node (ref "JP43") (pin "1") (pinfunction "1_1") (pintype "passive"))
      (node (ref "JP43") (pin "2") (pinfunction "2_2") (pintype "passive"))
      (node (ref "JP43") (pin "3") (pinfunction "3_3") (pintype "passive"))
      (node (ref "JP43") (pin "4") (pinfunction "4_4") (pintype "passive"))
      (node (ref "JP43") (pin "5") (pinfunction "5_5") (pintype "passive"))
    )
    (net (code "44") (name "Net-(JP44-Pad1)") (class "Default")
      (node (ref "JP44") (pin "1") (pinfunction "1_1") (pintype "passive"))
      (node (ref "JP44") (pin "2") (pinfunction "2_2") (pintype "passive"))
      (node (ref "JP44") (pin "3") (pinfunction "3_3") (pintype "passive"))
      (node (ref "JP44") (pin "4") (pinfunction "4_4") (pintype "passive"))
      (node (ref "JP44") (pin "5") (pinfunction "5_5") (pintype "passive"))
    )
    (net (code "45") (name "Net-(JP45-Pad1)") (class "Default")
      (node (ref "JP45") (pin "1") (pinfunction "1_1") (pintype "passive"))
      (node (ref "JP45") (pin "2") (pinfunction "2_2") (pintype "passive"))
      (node (ref "JP45") (pin "3") (pinfunction "3_3") (pintype "passive"))
      (node (ref "JP45") (pin "4") (pinfunction "4_4") (pintype "passive"))
      (node (ref "JP45") (pin "5") (pinfunction "5_5") (pintype "passive"))
    )
    (net (code "46") (name "Net-(JP46-Pad1)") (class "Default")
      (node (ref "JP46") (pin "1") (pinfunction "1_1") (pintype "passive"))
      (node (ref "JP46") (pin "2") (pinfunction "2_2") (pintype "passive"))
      (node (ref "JP46") (pin "3") (pinfunction "3_3") (pintype "passive"))
      (node (ref "JP46") (pin "4") (pinfunction "4_4") (pintype "passive"))
      (node (ref "JP46") (pin "5") (pinfunction "5_5") (pintype "passive"))
    )
    (net (code "47") (name "Net-(JP47-Pad1)") (class "Default")
      (node (ref "JP47") (pin "1") (pinfunction "1_1") (pintype "passive"))
      (node (ref "JP47") (pin "2") (pinfunction "2_2") (pintype "passive"))
      (node (ref "JP47") (pin "3") (pinfunction "3_3") (pintype "passive"))
      (node (ref "JP47") (pin "4") (pinfunction "4_4") (pintype "passive"))
      (node (ref "JP47") (pin "5") (pinfunction "5_5") (pintype "passive"))
    )
    (net (code "48") (name "Net-(JP48-Pad1)") (class "Default")
      (node (ref "JP48") (pin "1") (pinfunction "1_1") (pintype "passive"))
      (node (ref "JP48") (pin "2") (pinfunction "2_2") (pintype "passive"))
      (node (ref "JP48") (pin "3") (pinfunction "3_3") (pintype "passive"))
      (node (ref "JP48") (pin "4") (pinfunction "4_4") (pintype "passive"))
      (node (ref "JP48") (pin "5") (pinfunction "5_5") (pintype "passive"))
    )
    (net (code "49") (name "Net-(JP49-Pad1)") (class "Default")
      (node (ref "JP49") (pin "1") (pinfunction "1_1") (pintype "passive"))
      (node (ref "JP49") (pin "2") (pinfunction "2_2") (pintype "passive"))
      (node (ref "JP49") (pin "3") (pinfunction "3_3") (pintype "passive"))
      (node (ref "JP49") (pin "4") (pinfunction "4_4") (pintype "passive"))
      (node (ref "JP49") (pin "5") (pinfunction "5_5") (pintype "passive"))
    )
    (net (code "50") (name "Net-(JP50-Pad1)") (class "Default")
      (node (ref "JP50") (pin "1") (pinfunction "1_1") (pintype "passive"))
      (node (ref "JP50") (pin "2") (pinfunction "2_2") (pintype "passive"))
      (node (ref "JP50") (pin "3") (pinfunction "3_3") (pintype "passive"))
      (node (ref "JP50") (pin "4") (pinfunction "4_4") (pintype "passive"))
      (node (ref "JP50") (pin "5") (pinfunction "5_5") (pintype "passive"))
    )
    (net (code "51") (name "Net-(JP51-Pad1)") (class "Default")
      (node (ref "JP51") (pin "1") (pinfunction "1_1") (pintype "passive"))
      (node (ref "JP51") (pin "2") (pinfunction "2_2") (pintype "passive"))
      (node (ref "JP51") (pin "3") (pinfunction "3_3") (pintype "passive"))
      (node (ref "JP51") (pin "4") (pinfunction "4_4") (pintype "passive"))
      (node (ref "JP51") (pin "5") (pinfunction "5_5") (pintype "passive"))
    )
    (net (code "52") (name "Net-(JP52-Pad1)") (class "Default")
      (node (ref "JP52") (pin "1") (pinfunction "1_1") (pintype "passive"))
      (node (ref "JP52") (pin "2") (pinfunction "2_2") (pintype "passive"))
      (node (ref "JP52") (pin "3") (pinfunction "3_3") (pintype "passive"))
      (node (ref "JP52") (pin "4") (pinfunction "4_4") (pintype "passive"))
      (node (ref "JP52") (pin "5") (pinfunction "5_5") (pintype "passive"))
    )
    (net (code "53") (name "Net-(JP53-Pad1)") (class "Default")
      (node (ref "JP53") (pin "1") (pinfunction "1_1") (pintype "passive"))
      (node (ref "JP53") (pin "2") (pinfunction "2_2") (pintype "passive"))
      (node (ref "JP53") (pin "3") (pinfunction "3_3") (pintype "passive"))
      (node (ref "JP53") (pin "4") (pinfunction "4_4") (pintype "passive"))
      (node (ref "JP53") (pin "5") (pinfunction "5_5") (pintype "passive"))
    )
    (net (code "54") (name "Net-(JP54-Pad1)") (class "Default")
      (node (ref "JP54") (pin "1") (pinfunction "1_1") (pintype "passive"))
      (node (ref "JP54") (pin "2") (pinfunction "2_2") (pintype "passive"))
      (node (ref "JP54") (pin "3") (pinfunction "3_3") (pintype "passive"))
      (node (ref "JP54") (pin "4") (pinfunction "4_4") (pintype "passive"))
      (node (ref "JP54") (pin "5") (pinfunction "5_5") (pintype "passive"))
    )
    (net (code "55") (name "Net-(JP55-Pad1)") (class "Default")
      (node (ref "JP55") (pin "1") (pinfunction "1_1") (pintype "passive"))
      (node (ref "JP55") (pin "2") (pinfunction "2_2") (pintype "passive"))
      (node (ref "JP55") (pin "3") (pinfunction "3_3") (pintype "passive"))
      (node (ref "JP55") (pin "4") (pinfunction "4_4") (pintype "passive"))
      (node (ref "JP55") (pin "5") (pinfunction "5_5") (pintype "passive"))
    )
    (net (code "56") (name "Net-(JP56-Pad1)") (class "Default")
      (node (ref "JP56") (pin "1") (pinfunction "1_1") (pintype "passive"))
      (node (ref "JP56") (pin "2") (pinfunction "2_2") (pintype "passive"))
      (node (ref "JP56") (pin "3") (pinfunction "3_3") (pintype "passive"))
      (node (ref "JP56") (pin "4") (pinfunction "4_4") (pintype "passive"))
      (node (ref "JP56") (pin "5") (pinfunction "5_5") (pintype "passive"))
    )
    (net (code "57") (name "Net-(JP57-Pad1)") (class "Default")
      (node (ref "JP57") (pin "1") (pinfunction "1_1") (pintype "passive"))
      (node (ref "JP57") (pin "2") (pinfunction "2_2") (pintype "passive"))
      (node (ref "JP57") (pin "3") (pinfunction "3_3") (pintype "passive"))
      (node (ref "JP57") (pin "4") (pinfunction "4_4") (pintype "passive"))
      (node (ref "JP57") (pin "5") (pinfunction "5_5") (pintype "passive"))
    )
    (net (code "58") (name "Net-(JP58-Pad1)") (class "Default")
      (node (ref "JP58") (pin "1") (pinfunction "1_1") (pintype "passive"))
      (node (ref "JP58") (pin "2") (pinfunction "2_2") (pintype "passive"))
      (node (ref "JP58") (pin "3") (pinfunction "3_3") (pintype "passive"))
      (node (ref "JP58") (pin "4") (pinfunction "4_4") (pintype "passive"))
      (node (ref "JP58") (pin "5") (pinfunction "5_5") (pintype "passive"))
    )
    (net (code "59") (name "Net-(JP59-Pad1)") (class "Default")
      (node (ref "JP59") (pin "1") (pinfunction "1_1") (pintype "passive"))
      (node (ref "JP59") (pin "2") (pinfunction "2_2") (pintype "passive"))
      (node (ref "JP59") (pin "3") (pinfunction "3_3") (pintype "passive"))
      (node (ref "JP59") (pin "4") (pinfunction "4_4") (pintype "passive"))
      (node (ref "JP59") (pin "5") (pinfunction "5_5") (pintype "passive"))
    )
    (net (code "60") (name "Net-(JP60-Pad1)") (class "Default")
      (node (ref "JP60") (pin "1") (pinfunction "1_1") (pintype "passive"))
      (node (ref "JP60") (pin "2") (pinfunction "2_2") (pintype "passive"))
      (node (ref "JP60") (pin "3") (pinfunction "3_3") (pintype "passive"))
      (node (ref "JP60") (pin "4") (pinfunction "4_4") (pintype "passive"))
      (node (ref "JP60") (pin "5") (pinfunction "5_5") (pintype "passive"))
    )
    (net (code "61") (name "Net-(JP61-Pad1)") (class "Default")
      (node (ref "JP61") (pin "1") (pinfunction "1_1") (pintype "passive"))
      (node (ref "JP61") (pin "2") (pinfunction "2_2") (pintype "passive"))
      (node (ref "JP61") (pin "3") (pinfunction "3_3") (pintype "passive"))
      (node (ref "JP61") (pin "4") (pinfunction "4_4") (pintype "passive"))
      (node (ref "JP61") (pin "5") (pinfunction "5_5") (pintype "passive"))
    )
    (net (code "62") (name "Net-(JP62-Pad1)") (class "Default")
      (node (ref "JP62") (pin "1") (pinfunction "1_1") (pintype "passive"))
      (node (ref "JP62") (pin "2") (pinfunction "2_2") (pintype "passive"))
      (node (ref "JP62") (pin "3") (pinfunction "3_3") (pintype "passive"))
      (node (ref "JP62") (pin "4") (pinfunction "4_4") (pintype "passive"))
      (node (ref "JP62") (pin "5") (pinfunction "5_5") (pintype "passive"))
    )
    (net (code "63") (name "Net-(JP63-Pad1)") (class "Default")
      (node (ref "JP63") (pin "1") (pinfunction "1_1") (pintype "passive"))
      (node (ref "JP63") (pin "2") (pinfunction "2_2") (pintype "passive"))
      (node (ref "JP63") (pin "3") (pinfunction "3_3") (pintype "passive"))
      (node (ref "JP63") (pin "4") (pinfunction "4_4") (pintype "passive"))
      (node (ref "JP63") (pin "5") (pinfunction "5_5") (pintype "passive"))
    )
    (net (code "64") (name "Net-(JP64-Pad1)") (class "Default")
      (node (ref "JP64") (pin "1") (pinfunction "1_1") (pintype "passive"))
      (node (ref "JP64") (pin "2") (pinfunction "2_2") (pintype "passive"))
      (node (ref "JP64") (pin "3") (pinfunction "3_3") (pintype "passive"))
      (node (ref "JP64") (pin "4") (pinfunction "4_4") (pintype "passive"))
      (node (ref "JP64") (pin "5") (pinfunction "5_5") (pintype "passive"))
    )
    (net (code "65") (name "Net-(S1-P$1)") (class "Default")
      (node (ref "JP66") (pin "1") (pinfunction "1_1") (pintype "passive"))
      (node (ref "S1") (pin "P1") (pinfunction "P$1_P1") (pintype "bidirectional"))
    )
    (net (code "66") (name "Net-(S2-P$1)") (class "Default")
      (node (ref "JP65") (pin "1") (pinfunction "1_1") (pintype "passive"))
      (node (ref "S2") (pin "P1") (pinfunction "P$1_P1") (pintype "bidirectional"))
    )
    (net (code "67") (name "Net-(S3-P$1)") (class "Default")
      (node (ref "JP67") (pin "1") (pinfunction "1_1") (pintype "passive"))
      (node (ref "S3") (pin "P1") (pinfunction "P$1_P1") (pintype "bidirectional"))
    )
    (net (code "68") (name "Net-(S4-P$1)") (class "Default")
      (node (ref "JP68") (pin "1") (pinfunction "1_1") (pintype "passive"))
      (node (ref "S4") (pin "P1") (pinfunction "P$1_P1") (pintype "bidirectional"))
    )
  )
)
